# trb-1_v1.net
KiCad netlist of a schematic drawn in EAGLE
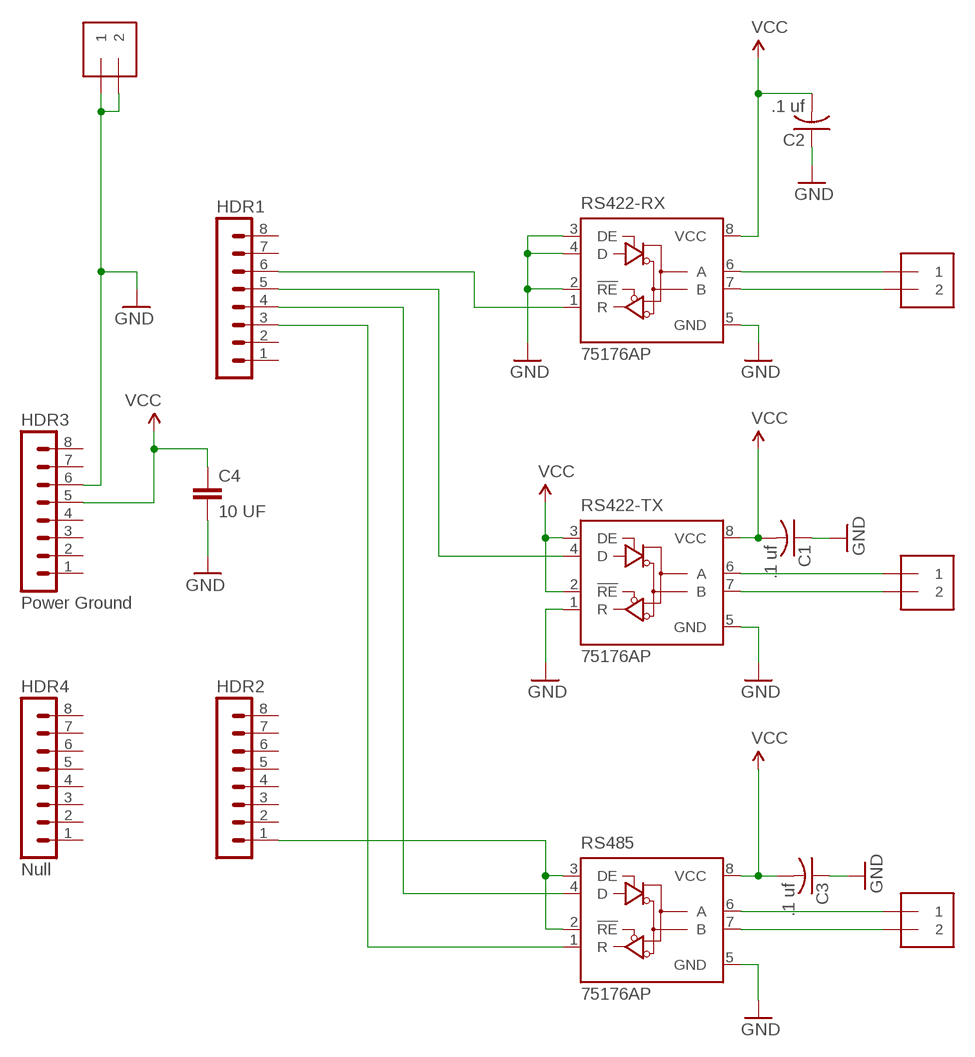
[diagram p0: schematic, sheet 1]

(export (version "E")
  (design (tool "Eeschema 10.0.6"))
  (components
    (comp (ref "C1")
      (value ".1 uf")
      (footprint "eagle-import:C0805")
      (libsource (lib "eagle-import") (part "C-USC0805"))
    )
    (comp (ref "C2")
      (value ".1 uf")
      (footprint "eagle-import:C0805")
      (libsource (lib "eagle-import") (part "C-USC0805"))
    )
    (comp (ref "C3")
      (value ".1 uf")
      (footprint "eagle-import:C0805")
      (libsource (lib "eagle-import") (part "C-USC0805"))
    )
    (comp (ref "C4")
      (value "10 UF")
      (footprint "eagle-import:0805-CAP")
      (libsource (lib "eagle-import") (part "10UF10V10%(0805)"))
    )
    (comp (ref "HDR1")
      (value "MA08-1")
      (footprint "eagle-import:MA08-1")
      (libsource (lib "eagle-import") (part "MA08-1"))
    )
    (comp (ref "HDR2")
      (value "MA08-1")
      (footprint "eagle-import:MA08-1")
      (libsource (lib "eagle-import") (part "MA08-1"))
    )
    (comp (ref "HDR3")
      (value "Power Ground")
      (footprint "eagle-import:MA08-1")
      (libsource (lib "eagle-import") (part "MA08-1"))
    )
    (comp (ref "HDR4")
      (value "Null")
      (footprint "eagle-import:MA08-1")
      (libsource (lib "eagle-import") (part "MA08-1"))
    )
    (comp (ref "J1")
      (value "1X2-3.5MM")
      (footprint "eagle-import:1X2-3.5MM")
      (libsource (lib "eagle-import") (part "1X2-3.5MM"))
    )
    (comp (ref "RS422-RX")
      (value "75176AP")
      (footprint "eagle-import:DIL08")
      (fields (field (name "MF") "TEXAS INSTRUMENTS") (field (name "MPN") "SN75176AP"))
      (libsource (lib "eagle-import") (part "75176AP"))
    )
    (comp (ref "RS422-RX1")
      (value "1X2-3.5MM")
      (footprint "eagle-import:1X2-3.5MM")
      (libsource (lib "eagle-import") (part "1X2-3.5MM"))
    )
    (comp (ref "RS422-TX")
      (value "75176AP")
      (footprint "eagle-import:DIL08")
      (fields (field (name "MF") "TEXAS INSTRUMENTS") (field (name "MPN") "SN75176AP"))
      (libsource (lib "eagle-import") (part "75176AP"))
    )
    (comp (ref "RS422-TX1")
      (value "1X2-3.5MM")
      (footprint "eagle-import:1X2-3.5MM")
      (libsource (lib "eagle-import") (part "1X2-3.5MM"))
    )
    (comp (ref "RS485")
      (value "75176AP")
      (footprint "eagle-import:DIL08")
      (fields (field (name "MF") "TEXAS INSTRUMENTS") (field (name "MPN") "SN75176AP"))
      (libsource (lib "eagle-import") (part "75176AP"))
    )
    (comp (ref "RS485-TXRX")
      (value "1X2-3.5MM")
      (footprint "eagle-import:1X2-3.5MM")
      (libsource (lib "eagle-import") (part "1X2-3.5MM"))
    )
  )
  (nets
    (net (code "1") (name "GND") (class "Default")
      (node (ref "C1") (pin "1") (pinfunction "1_1") (pintype "passive"))
      (node (ref "C2") (pin "1") (pinfunction "1_1") (pintype "passive"))
      (node (ref "C3") (pin "1") (pinfunction "1_1") (pintype "passive"))
      (node (ref "C4") (pin "2") (pinfunction "2_2") (pintype "passive"))
      (node (ref "HDR3") (pin "6") (pinfunction "6_6") (pintype "passive"))
      (node (ref "J1") (pin "1") (pinfunction "1_1") (pintype "passive"))
      (node (ref "J1") (pin "2") (pinfunction "2_2") (pintype "passive"))
      (node (ref "RS422-RX") (pin "2") (pinfunction "~{RE}_2") (pintype "input"))
      (node (ref "RS422-RX") (pin "3") (pinfunction "DE_3") (pintype "input"))
      (node (ref "RS422-RX") (pin "4") (pinfunction "D_4") (pintype "input"))
      (node (ref "RS422-RX") (pin "5") (pinfunction "GND_5") (pintype "power_in"))
      (node (ref "RS422-TX") (pin "1") (pinfunction "R_1") (pintype "input"))
      (node (ref "RS422-TX") (pin "5") (pinfunction "GND_5") (pintype "power_in"))
      (node (ref "RS485") (pin "5") (pinfunction "GND_5") (pintype "power_in"))
    )
    (net (code "2") (name "Net-(RS422-RX-A)") (class "Default")
      (node (ref "RS422-RX") (pin "6") (pinfunction "A_6") (pintype "output"))
      (node (ref "RS422-RX1") (pin "1") (pinfunction "1_1") (pintype "passive"))
    )
    (net (code "3") (name "Net-(RS422-RX-B)") (class "Default")
      (node (ref "RS422-RX") (pin "7") (pinfunction "B_7") (pintype "output"))
      (node (ref "RS422-RX1") (pin "2") (pinfunction "2_2") (pintype "passive"))
    )
    (net (code "4") (name "Net-(RS422-RX-R)") (class "Default")
      (node (ref "HDR1") (pin "6") (pinfunction "6_6") (pintype "passive"))
      (node (ref "RS422-RX") (pin "1") (pinfunction "R_1") (pintype "input"))
    )
    (net (code "5") (name "Net-(RS422-TX-A)") (class "Default")
      (node (ref "RS422-TX") (pin "6") (pinfunction "A_6") (pintype "output"))
      (node (ref "RS422-TX1") (pin "1") (pinfunction "1_1") (pintype "passive"))
    )
    (net (code "6") (name "Net-(RS422-TX-B)") (class "Default")
      (node (ref "RS422-TX") (pin "7") (pinfunction "B_7") (pintype "output"))
      (node (ref "RS422-TX1") (pin "2") (pinfunction "2_2") (pintype "passive"))
    )
    (net (code "7") (name "Net-(RS422-TX-D)") (class "Default")
      (node (ref "HDR1") (pin "5") (pinfunction "5_5") (pintype "passive"))
      (node (ref "RS422-TX") (pin "4") (pinfunction "D_4") (pintype "input"))
    )
    (net (code "8") (name "Net-(RS485-A)") (class "Default")
      (node (ref "RS485") (pin "6") (pinfunction "A_6") (pintype "output"))
      (node (ref "RS485-TXRX") (pin "1") (pinfunction "1_1") (pintype "passive"))
    )
    (net (code "9") (name "Net-(RS485-B)") (class "Default")
      (node (ref "RS485") (pin "7") (pinfunction "B_7") (pintype "output"))
      (node (ref "RS485-TXRX") (pin "2") (pinfunction "2_2") (pintype "passive"))
    )
    (net (code "10") (name "Net-(RS485-D)") (class "Default")
      (node (ref "HDR1") (pin "4") (pinfunction "4_4") (pintype "passive"))
      (node (ref "RS485") (pin "4") (pinfunction "D_4") (pintype "input"))
    )
    (net (code "11") (name "Net-(RS485-DE)") (class "Default")
      (node (ref "HDR2") (pin "1") (pinfunction "1_1") (pintype "passive"))
      (node (ref "RS485") (pin "2") (pinfunction "~{RE}_2") (pintype "input"))
      (node (ref "RS485") (pin "3") (pinfunction "DE_3") (pintype "input"))
    )
    (net (code "12") (name "Net-(RS485-R)") (class "Default")
      (node (ref "HDR1") (pin "3") (pinfunction "3_3") (pintype "passive"))
      (node (ref "RS485") (pin "1") (pinfunction "R_1") (pintype "input"))
    )
    (net (code "13") (name "VCC") (class "Default")
      (node (ref "C1") (pin "2") (pinfunction "2_2") (pintype "passive"))
      (node (ref "C2") (pin "2") (pinfunction "2_2") (pintype "passive"))
      (node (ref "C3") (pin "2") (pinfunction "2_2") (pintype "passive"))
      (node (ref "C4") (pin "1") (pinfunction "1_1") (pintype "passive"))
      (node (ref "HDR3") (pin "5") (pinfunction "5_5") (pintype "passive"))
      (node (ref "RS422-RX") (pin "8") (pinfunction "VCC_8") (pintype "power_in"))
      (node (ref "RS422-TX") (pin "2") (pinfunction "~{RE}_2") (pintype "input"))
      (node (ref "RS422-TX") (pin "3") (pinfunction "DE_3") (pintype "input"))
      (node (ref "RS422-TX") (pin "8") (pinfunction "VCC_8") (pintype "power_in"))
      (node (ref "RS485") (pin "8") (pinfunction "VCC_8") (pintype "power_in"))
    )
    (net (code "14") (name "unconnected-(HDR1-Pad1)") (class "Default")
      (node (ref "HDR1") (pin "1") (pinfunction "1_1") (pintype "passive"))
    )
    (net (code "15") (name "unconnected-(HDR1-Pad2)") (class "Default")
      (node (ref "HDR1") (pin "2") (pinfunction "2_2") (pintype "passive"))
    )
    (net (code "16") (name "unconnected-(HDR1-Pad7)") (class "Default")
      (node (ref "HDR1") (pin "7") (pinfunction "7_7") (pintype "passive"))
    )
    (net (code "17") (name "unconnected-(HDR1-Pad8)") (class "Default")
      (node (ref "HDR1") (pin "8") (pinfunction "8_8") (pintype "passive"))
    )
    (net (code "18") (name "unconnected-(HDR2-Pad2)") (class "Default")
      (node (ref "HDR2") (pin "2") (pinfunction "2_2") (pintype "passive"))
    )
    (net (code "19") (name "unconnected-(HDR2-Pad3)") (class "Default")
      (node (ref "HDR2") (pin "3") (pinfunction "3_3") (pintype "passive"))
    )
    (net (code "20") (name "unconnected-(HDR2-Pad4)") (class "Default")
      (node (ref "HDR2") (pin "4") (pinfunction "4_4") (pintype "passive"))
    )
    (net (code "21") (name "unconnected-(HDR2-Pad5)") (class "Default")
      (node (ref "HDR2") (pin "5") (pinfunction "5_5") (pintype "passive"))
    )
    (net (code "22") (name "unconnected-(HDR2-Pad6)") (class "Default")
      (node (ref "HDR2") (pin "6") (pinfunction "6_6") (pintype "passive"))
    )
    (net (code "23") (name "unconnected-(HDR2-Pad7)") (class "Default")
      (node (ref "HDR2") (pin "7") (pinfunction "7_7") (pintype "passive"))
    )
    (net (code "24") (name "unconnected-(HDR2-Pad8)") (class "Default")
      (node (ref "HDR2") (pin "8") (pinfunction "8_8") (pintype "passive"))
    )
    (net (code "25") (name "unconnected-(HDR3-Pad1)") (class "Default")
      (node (ref "HDR3") (pin "1") (pinfunction "1_1") (pintype "passive"))
    )
    (net (code "26") (name "unconnected-(HDR3-Pad2)") (class "Default")
      (node (ref "HDR3") (pin "2") (pinfunction "2_2") (pintype "passive"))
    )
    (net (code "27") (name "unconnected-(HDR3-Pad3)") (class "Default")
      (node (ref "HDR3") (pin "3") (pinfunction "3_3") (pintype "passive"))
    )
    (net (code "28") (name "unconnected-(HDR3-Pad4)") (class "Default")
      (node (ref "HDR3") (pin "4") (pinfunction "4_4") (pintype "passive"))
    )
    (net (code "29") (name "unconnected-(HDR3-Pad7)") (class "Default")
      (node (ref "HDR3") (pin "7") (pinfunction "7_7") (pintype "passive"))
    )
    (net (code "30") (name "unconnected-(HDR3-Pad8)") (class "Default")
      (node (ref "HDR3") (pin "8") (pinfunction "8_8") (pintype "passive"))
    )
    (net (code "31") (name "unconnected-(HDR4-Pad1)") (class "Default")
      (node (ref "HDR4") (pin "1") (pinfunction "1_1") (pintype "passive"))
    )
    (net (code "32") (name "unconnected-(HDR4-Pad2)") (class "Default")
      (node (ref "HDR4") (pin "2") (pinfunction "2_2") (pintype "passive"))
    )
    (net (code "33") (name "unconnected-(HDR4-Pad3)") (class "Default")
      (node (ref "HDR4") (pin "3") (pinfunction "3_3") (pintype "passive"))
    )
    (net (code "34") (name "unconnected-(HDR4-Pad4)") (class "Default")
      (node (ref "HDR4") (pin "4") (pinfunction "4_4") (pintype "passive"))
    )
    (net (code "35") (name "unconnected-(HDR4-Pad5)") (class "Default")
      (node (ref "HDR4") (pin "5") (pinfunction "5_5") (pintype "passive"))
    )
    (net (code "36") (name "unconnected-(HDR4-Pad6)") (class "Default")
      (node (ref "HDR4") (pin "6") (pinfunction "6_6") (pintype "passive"))
    )
    (net (code "37") (name "unconnected-(HDR4-Pad7)") (class "Default")
      (node (ref "HDR4") (pin "7") (pinfunction "7_7") (pintype "passive"))
    )
    (net (code "38") (name "unconnected-(HDR4-Pad8)") (class "Default")
      (node (ref "HDR4") (pin "8") (pinfunction "8_8") (pintype "passive"))
    )
  )
)
